# 07_eMMC.net
KiCad netlist of a schematic drawn in Altium Designer
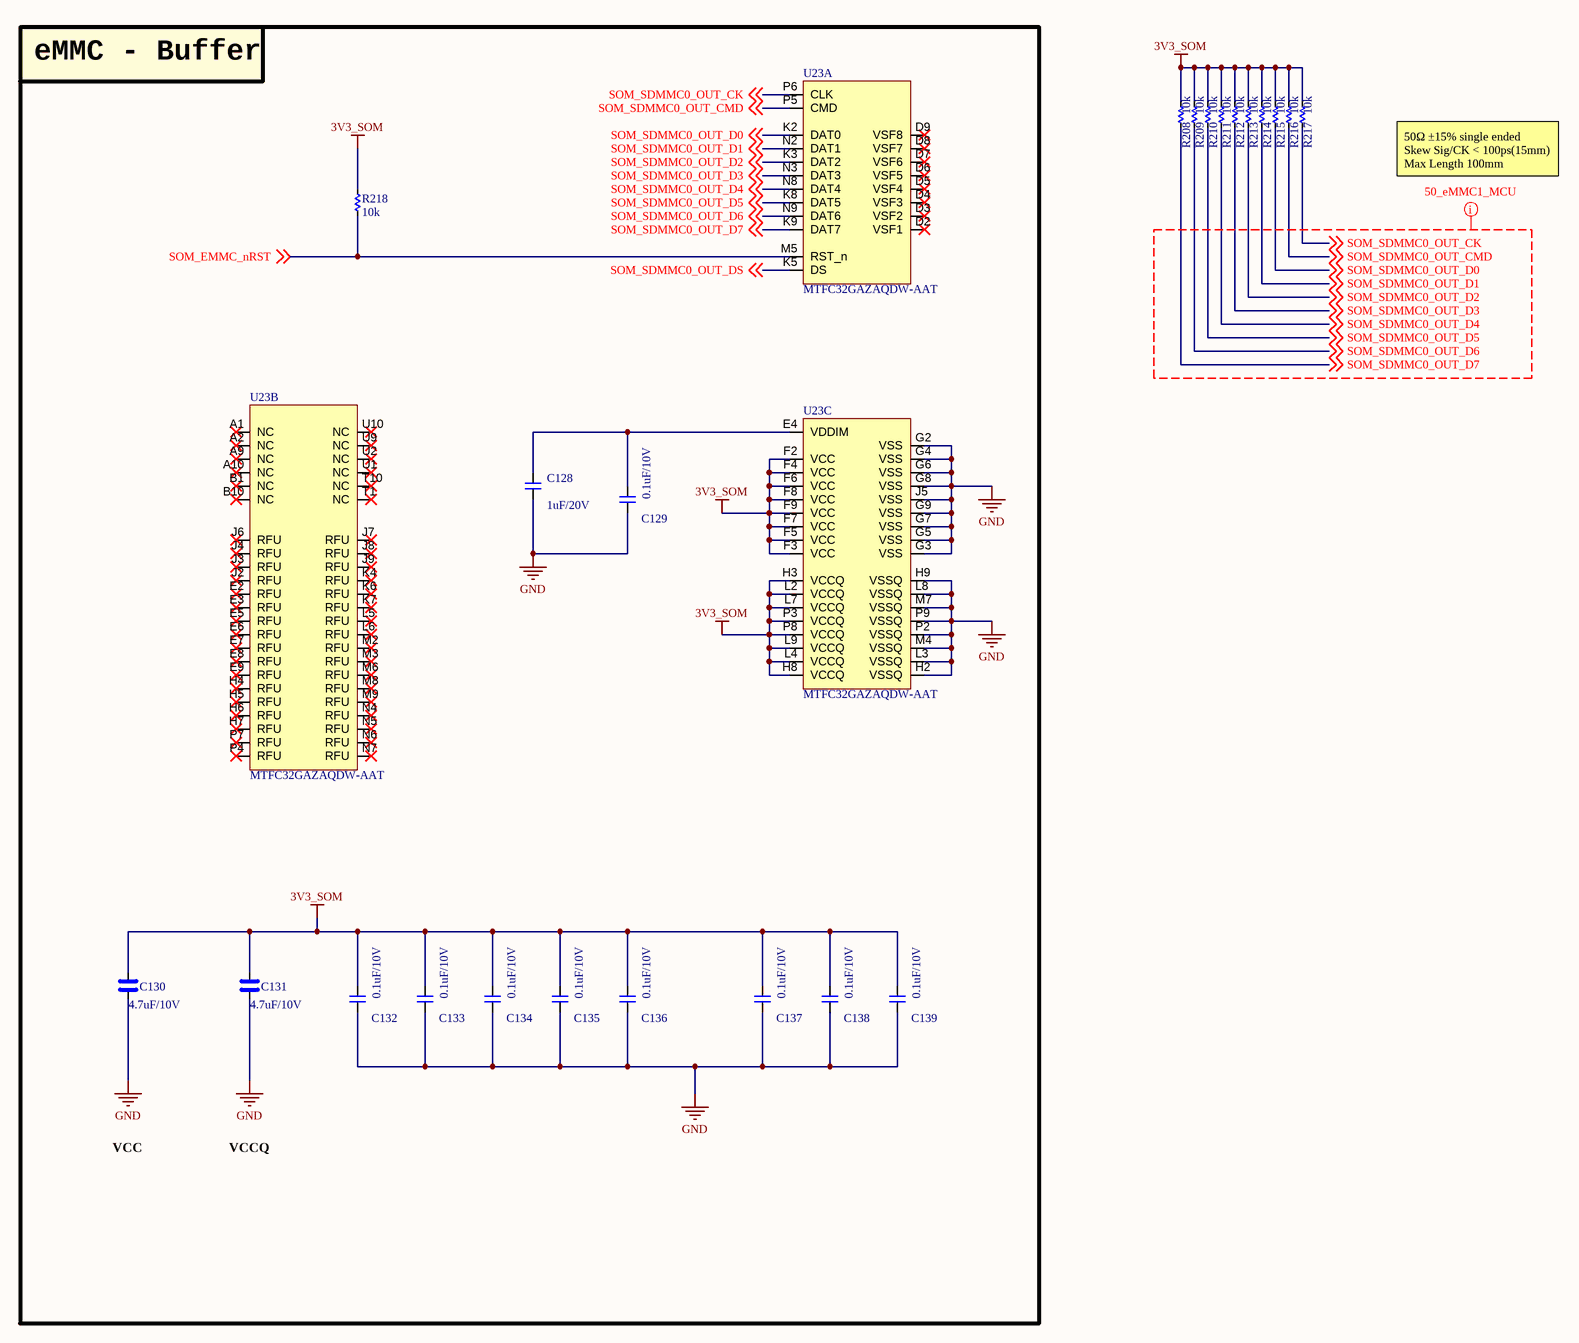
[diagram p0: 07_eMMC.SchDoc]

(export (version "E")
  (design (tool "Eeschema 10.0.6"))
  (components
    (comp (ref "C128")
      (value "1uF/20V")
      (footprint "CAP_C_1005X60")
      (description "CAP CHIP")
      (libsource (lib "LABLIB") (part "_CAP_C_2"))
    )
    (comp (ref "C129")
      (value "0.1uF/10V")
      (footprint "CAP_C_1005X60")
      (description "CAP CHIP")
      (libsource (lib "LABLIB") (part "_CAP_C_2"))
    )
    (comp (ref "C130")
      (value "4.7uF/10V")
      (footprint "CAP_C_1608X80")
      (description "CAP CHIP High Value")
      (libsource (lib "LABLIB") (part "_CAP_C_High_2"))
    )
    (comp (ref "C131")
      (value "4.7uF/10V")
      (footprint "CAP_C_1608X80")
      (description "CAP CHIP High Value")
      (libsource (lib "LABLIB") (part "_CAP_C_High_2"))
    )
    (comp (ref "C132")
      (value "0.1uF/10V")
      (footprint "CAP_C_1005X60")
      (description "CAP CHIP")
      (libsource (lib "LABLIB") (part "_CAP_C_2"))
    )
    (comp (ref "C133")
      (value "0.1uF/10V")
      (footprint "CAP_C_1005X60")
      (description "CAP CHIP")
      (libsource (lib "LABLIB") (part "_CAP_C_2"))
    )
    (comp (ref "C134")
      (value "0.1uF/10V")
      (footprint "CAP_C_1005X60")
      (description "CAP CHIP")
      (libsource (lib "LABLIB") (part "_CAP_C_2"))
    )
    (comp (ref "C135")
      (value "0.1uF/10V")
      (footprint "CAP_C_1005X60")
      (description "CAP CHIP")
      (libsource (lib "LABLIB") (part "_CAP_C_2"))
    )
    (comp (ref "C136")
      (value "0.1uF/10V")
      (footprint "CAP_C_1005X60")
      (description "CAP CHIP")
      (libsource (lib "LABLIB") (part "_CAP_C_2"))
    )
    (comp (ref "C137")
      (value "0.1uF/10V")
      (footprint "CAP_C_1005X60")
      (description "CAP CHIP")
      (libsource (lib "LABLIB") (part "_CAP_C_2"))
    )
    (comp (ref "C138")
      (value "0.1uF/10V")
      (footprint "CAP_C_1005X60")
      (description "CAP CHIP")
      (libsource (lib "LABLIB") (part "_CAP_C_2"))
    )
    (comp (ref "C139")
      (value "0.1uF/10V")
      (footprint "CAP_C_1005X60")
      (description "CAP CHIP")
      (libsource (lib "LABLIB") (part "_CAP_C_2"))
    )
    (comp (ref "R208")
      (value "10k")
      (footprint "RES_C_1005X40")
      (description "RES")
      (libsource (lib "LABLIB") (part "_RES_B_2"))
    )
    (comp (ref "R209")
      (value "10k")
      (footprint "RES_C_1005X40")
      (description "RES")
      (libsource (lib "LABLIB") (part "_RES_B_2"))
    )
    (comp (ref "R210")
      (value "10k")
      (footprint "RES_C_1005X40")
      (description "RES")
      (libsource (lib "LABLIB") (part "_RES_B_2"))
    )
    (comp (ref "R211")
      (value "10k")
      (footprint "RES_C_1005X40")
      (description "RES")
      (libsource (lib "LABLIB") (part "_RES_B_2"))
    )
    (comp (ref "R212")
      (value "10k")
      (footprint "RES_C_1005X40")
      (description "RES")
      (libsource (lib "LABLIB") (part "_RES_B_2"))
    )
    (comp (ref "R213")
      (value "10k")
      (footprint "RES_C_1005X40")
      (description "RES")
      (libsource (lib "LABLIB") (part "_RES_B_2"))
    )
    (comp (ref "R214")
      (value "10k")
      (footprint "RES_C_1005X40")
      (description "RES")
      (libsource (lib "LABLIB") (part "_RES_B_2"))
    )
    (comp (ref "R215")
      (value "10k")
      (footprint "RES_C_1005X40")
      (description "RES")
      (libsource (lib "LABLIB") (part "_RES_B_2"))
    )
    (comp (ref "R216")
      (value "10k")
      (footprint "RES_C_1005X40")
      (description "RES")
      (libsource (lib "LABLIB") (part "_RES_B_2"))
    )
    (comp (ref "R217")
      (value "10k")
      (footprint "RES_C_1005X40")
      (description "RES")
      (libsource (lib "LABLIB") (part "_RES_B_2"))
    )
    (comp (ref "R218")
      (value "10k")
      (footprint "RES_C_1005X40")
      (description "RES")
      (libsource (lib "LABLIB") (part "_RES_B_2"))
    )
    (comp (ref "U23")
      (value "MTFC32GAZAQDW-AAT")
      (footprint "BGA_100_C_100P_10X17_1400X1800X150")
      (libsource (lib "emmc_nofootprint") (part "MTFC32GAZAQDW-AAT"))
    )
  )
  (nets
    (net (code "1") (name "3V3_SOM") (class "Default")
      (node (ref "C130") (pin "2") (pinfunction "2_2") (pintype "passive"))
      (node (ref "C131") (pin "2") (pinfunction "2_2") (pintype "passive"))
      (node (ref "C132") (pin "2") (pinfunction "2_2") (pintype "passive"))
      (node (ref "C133") (pin "2") (pinfunction "2_2") (pintype "passive"))
      (node (ref "C134") (pin "2") (pinfunction "2_2") (pintype "passive"))
      (node (ref "C135") (pin "2") (pinfunction "2_2") (pintype "passive"))
      (node (ref "C136") (pin "2") (pinfunction "2_2") (pintype "passive"))
      (node (ref "C137") (pin "2") (pinfunction "2_2") (pintype "passive"))
      (node (ref "C138") (pin "2") (pinfunction "2_2") (pintype "passive"))
      (node (ref "C139") (pin "2") (pinfunction "2_2") (pintype "passive"))
      (node (ref "R208") (pin "2") (pinfunction "2_2") (pintype "passive"))
      (node (ref "R209") (pin "2") (pinfunction "2_2") (pintype "passive"))
      (node (ref "R210") (pin "2") (pinfunction "2_2") (pintype "passive"))
      (node (ref "R211") (pin "2") (pinfunction "2_2") (pintype "passive"))
      (node (ref "R212") (pin "2") (pinfunction "2_2") (pintype "passive"))
      (node (ref "R213") (pin "2") (pinfunction "2_2") (pintype "passive"))
      (node (ref "R214") (pin "2") (pinfunction "2_2") (pintype "passive"))
      (node (ref "R215") (pin "2") (pinfunction "2_2") (pintype "passive"))
      (node (ref "R216") (pin "2") (pinfunction "2_2") (pintype "passive"))
      (node (ref "R217") (pin "2") (pinfunction "2_2") (pintype "passive"))
      (node (ref "R218") (pin "2") (pinfunction "2_2") (pintype "passive"))
      (node (ref "U23") (pin "F2") (pinfunction "VCC_F2") (pintype "passive"))
      (node (ref "U23") (pin "F3") (pinfunction "VCC_F3") (pintype "passive"))
      (node (ref "U23") (pin "F4") (pinfunction "VCC_F4") (pintype "passive"))
      (node (ref "U23") (pin "F5") (pinfunction "VCC_F5") (pintype "passive"))
      (node (ref "U23") (pin "F6") (pinfunction "VCC_F6") (pintype "passive"))
      (node (ref "U23") (pin "F7") (pinfunction "VCC_F7") (pintype "passive"))
      (node (ref "U23") (pin "F8") (pinfunction "VCC_F8") (pintype "passive"))
      (node (ref "U23") (pin "F9") (pinfunction "VCC_F9") (pintype "passive"))
      (node (ref "U23") (pin "H3") (pinfunction "VCCQ_H3") (pintype "passive"))
      (node (ref "U23") (pin "H8") (pinfunction "VCCQ_H8") (pintype "passive"))
      (node (ref "U23") (pin "L2") (pinfunction "VCCQ_L2") (pintype "passive"))
      (node (ref "U23") (pin "L4") (pinfunction "VCCQ_L4") (pintype "passive"))
      (node (ref "U23") (pin "L7") (pinfunction "VCCQ_L7") (pintype "passive"))
      (node (ref "U23") (pin "L9") (pinfunction "VCCQ_L9") (pintype "passive"))
      (node (ref "U23") (pin "P3") (pinfunction "VCCQ_P3") (pintype "passive"))
      (node (ref "U23") (pin "P8") (pinfunction "VCCQ_P8") (pintype "passive"))
    )
    (net (code "2") (name "GND") (class "Default")
      (node (ref "C128") (pin "1") (pinfunction "1_1") (pintype "passive"))
      (node (ref "C129") (pin "1") (pinfunction "1_1") (pintype "passive"))
      (node (ref "C130") (pin "1") (pinfunction "1_1") (pintype "passive"))
      (node (ref "C131") (pin "1") (pinfunction "1_1") (pintype "passive"))
      (node (ref "C132") (pin "1") (pinfunction "1_1") (pintype "passive"))
      (node (ref "C133") (pin "1") (pinfunction "1_1") (pintype "passive"))
      (node (ref "C134") (pin "1") (pinfunction "1_1") (pintype "passive"))
      (node (ref "C135") (pin "1") (pinfunction "1_1") (pintype "passive"))
      (node (ref "C136") (pin "1") (pinfunction "1_1") (pintype "passive"))
      (node (ref "C137") (pin "1") (pinfunction "1_1") (pintype "passive"))
      (node (ref "C138") (pin "1") (pinfunction "1_1") (pintype "passive"))
      (node (ref "C139") (pin "1") (pinfunction "1_1") (pintype "passive"))
      (node (ref "U23") (pin "G2") (pinfunction "VSS_G2") (pintype "passive"))
      (node (ref "U23") (pin "G3") (pinfunction "VSS_G3") (pintype "passive"))
      (node (ref "U23") (pin "G4") (pinfunction "VSS_G4") (pintype "passive"))
      (node (ref "U23") (pin "G5") (pinfunction "VSS_G5") (pintype "passive"))
      (node (ref "U23") (pin "G6") (pinfunction "VSS_G6") (pintype "passive"))
      (node (ref "U23") (pin "G7") (pinfunction "VSS_G7") (pintype "passive"))
      (node (ref "U23") (pin "G8") (pinfunction "VSS_G8") (pintype "passive"))
      (node (ref "U23") (pin "G9") (pinfunction "VSS_G9") (pintype "passive"))
      (node (ref "U23") (pin "H2") (pinfunction "VSSQ_H2") (pintype "passive"))
      (node (ref "U23") (pin "H9") (pinfunction "VSSQ_H9") (pintype "passive"))
      (node (ref "U23") (pin "J5") (pinfunction "VSS_J5") (pintype "passive"))
      (node (ref "U23") (pin "L3") (pinfunction "VSSQ_L3") (pintype "passive"))
      (node (ref "U23") (pin "L8") (pinfunction "VSSQ_L8") (pintype "passive"))
      (node (ref "U23") (pin "M4") (pinfunction "VSSQ_M4") (pintype "passive"))
      (node (ref "U23") (pin "M7") (pinfunction "VSSQ_M7") (pintype "passive"))
      (node (ref "U23") (pin "P2") (pinfunction "VSSQ_P2") (pintype "passive"))
      (node (ref "U23") (pin "P9") (pinfunction "VSSQ_P9") (pintype "passive"))
    )
    (net (code "3") (name "Net-(U23C-VDDIM)") (class "Default")
      (node (ref "C128") (pin "2") (pinfunction "2_2") (pintype "passive"))
      (node (ref "C129") (pin "2") (pinfunction "2_2") (pintype "passive"))
      (node (ref "U23") (pin "E4") (pinfunction "VDDIM_E4") (pintype "passive"))
    )
    (net (code "4") (name "SOM_EMMC_nRST") (class "Default")
      (node (ref "R218") (pin "1") (pinfunction "1_1") (pintype "passive"))
      (node (ref "U23") (pin "M5") (pinfunction "RST_n_M5") (pintype "passive"))
    )
    (net (code "5") (name "SOM_SDMMC0_OUT_CK") (class "Default")
      (node (ref "R217") (pin "1") (pinfunction "1_1") (pintype "passive"))
      (node (ref "U23") (pin "P6") (pinfunction "CLK_P6") (pintype "passive"))
    )
    (net (code "6") (name "SOM_SDMMC0_OUT_CMD") (class "Default")
      (node (ref "R216") (pin "1") (pinfunction "1_1") (pintype "passive"))
      (node (ref "U23") (pin "P5") (pinfunction "CMD_P5") (pintype "passive"))
    )
    (net (code "7") (name "SOM_SDMMC0_OUT_D0") (class "Default")
      (node (ref "R215") (pin "1") (pinfunction "1_1") (pintype "passive"))
      (node (ref "U23") (pin "K2") (pinfunction "DAT0_K2") (pintype "passive"))
    )
    (net (code "8") (name "SOM_SDMMC0_OUT_D1") (class "Default")
      (node (ref "R214") (pin "1") (pinfunction "1_1") (pintype "passive"))
      (node (ref "U23") (pin "N2") (pinfunction "DAT1_N2") (pintype "passive"))
    )
    (net (code "9") (name "SOM_SDMMC0_OUT_D2") (class "Default")
      (node (ref "R213") (pin "1") (pinfunction "1_1") (pintype "passive"))
      (node (ref "U23") (pin "K3") (pinfunction "DAT2_K3") (pintype "passive"))
    )
    (net (code "10") (name "SOM_SDMMC0_OUT_D3") (class "Default")
      (node (ref "R212") (pin "1") (pinfunction "1_1") (pintype "passive"))
      (node (ref "U23") (pin "N3") (pinfunction "DAT3_N3") (pintype "passive"))
    )
    (net (code "11") (name "SOM_SDMMC0_OUT_D4") (class "Default")
      (node (ref "R211") (pin "1") (pinfunction "1_1") (pintype "passive"))
      (node (ref "U23") (pin "N8") (pinfunction "DAT4_N8") (pintype "passive"))
    )
    (net (code "12") (name "SOM_SDMMC0_OUT_D5") (class "Default")
      (node (ref "R210") (pin "1") (pinfunction "1_1") (pintype "passive"))
      (node (ref "U23") (pin "K8") (pinfunction "DAT5_K8") (pintype "passive"))
    )
    (net (code "13") (name "SOM_SDMMC0_OUT_D6") (class "Default")
      (node (ref "R209") (pin "1") (pinfunction "1_1") (pintype "passive"))
      (node (ref "U23") (pin "N9") (pinfunction "DAT6_N9") (pintype "passive"))
    )
    (net (code "14") (name "SOM_SDMMC0_OUT_D7") (class "Default")
      (node (ref "R208") (pin "1") (pinfunction "1_1") (pintype "passive"))
      (node (ref "U23") (pin "K9") (pinfunction "DAT7_K9") (pintype "passive"))
    )
    (net (code "15") (name "SOM_SDMMC0_OUT_DS") (class "Default")
      (node (ref "U23") (pin "K5") (pinfunction "DS_K5") (pintype "passive"))
    )
    (net (code "16") (name "unconnected-(U23A-VSF1-PadD2)") (class "Default")
      (node (ref "U23") (pin "D2") (pinfunction "VSF1_D2") (pintype "passive+no_connect"))
    )
    (net (code "17") (name "unconnected-(U23A-VSF2-PadD3)") (class "Default")
      (node (ref "U23") (pin "D3") (pinfunction "VSF2_D3") (pintype "passive+no_connect"))
    )
    (net (code "18") (name "unconnected-(U23A-VSF3-PadD4)") (class "Default")
      (node (ref "U23") (pin "D4") (pinfunction "VSF3_D4") (pintype "passive+no_connect"))
    )
    (net (code "19") (name "unconnected-(U23A-VSF4-PadD5)") (class "Default")
      (node (ref "U23") (pin "D5") (pinfunction "VSF4_D5") (pintype "passive+no_connect"))
    )
    (net (code "20") (name "unconnected-(U23A-VSF5-PadD6)") (class "Default")
      (node (ref "U23") (pin "D6") (pinfunction "VSF5_D6") (pintype "passive+no_connect"))
    )
    (net (code "21") (name "unconnected-(U23A-VSF6-PadD7)") (class "Default")
      (node (ref "U23") (pin "D7") (pinfunction "VSF6_D7") (pintype "passive+no_connect"))
    )
    (net (code "22") (name "unconnected-(U23A-VSF7-PadD8)") (class "Default")
      (node (ref "U23") (pin "D8") (pinfunction "VSF7_D8") (pintype "passive+no_connect"))
    )
    (net (code "23") (name "unconnected-(U23A-VSF8-PadD9)") (class "Default")
      (node (ref "U23") (pin "D9") (pinfunction "VSF8_D9") (pintype "passive+no_connect"))
    )
    (net (code "24") (name "unconnected-(U23B-NC-PadA1)") (class "Default")
      (node (ref "U23") (pin "A1") (pinfunction "NC_A1") (pintype "passive+no_connect"))
    )
    (net (code "25") (name "unconnected-(U23B-NC-PadA2)") (class "Default")
      (node (ref "U23") (pin "A2") (pinfunction "NC_A2") (pintype "passive+no_connect"))
    )
    (net (code "26") (name "unconnected-(U23B-NC-PadA9)") (class "Default")
      (node (ref "U23") (pin "A9") (pinfunction "NC_A9") (pintype "passive+no_connect"))
    )
    (net (code "27") (name "unconnected-(U23B-NC-PadA10)") (class "Default")
      (node (ref "U23") (pin "A10") (pinfunction "NC_A10") (pintype "passive+no_connect"))
    )
    (net (code "28") (name "unconnected-(U23B-NC-PadB1)") (class "Default")
      (node (ref "U23") (pin "B1") (pinfunction "NC_B1") (pintype "passive+no_connect"))
    )
    (net (code "29") (name "unconnected-(U23B-NC-PadB10)") (class "Default")
      (node (ref "U23") (pin "B10") (pinfunction "NC_B10") (pintype "passive+no_connect"))
    )
    (net (code "30") (name "unconnected-(U23B-NC-PadT1)") (class "Default")
      (node (ref "U23") (pin "T1") (pinfunction "NC_T1") (pintype "passive+no_connect"))
    )
    (net (code "31") (name "unconnected-(U23B-NC-PadT10)") (class "Default")
      (node (ref "U23") (pin "T10") (pinfunction "NC_T10") (pintype "passive+no_connect"))
    )
    (net (code "32") (name "unconnected-(U23B-NC-PadU1)") (class "Default")
      (node (ref "U23") (pin "U1") (pinfunction "NC_U1") (pintype "passive+no_connect"))
    )
    (net (code "33") (name "unconnected-(U23B-NC-PadU2)") (class "Default")
      (node (ref "U23") (pin "U2") (pinfunction "NC_U2") (pintype "passive+no_connect"))
    )
    (net (code "34") (name "unconnected-(U23B-NC-PadU9)") (class "Default")
      (node (ref "U23") (pin "U9") (pinfunction "NC_U9") (pintype "passive+no_connect"))
    )
    (net (code "35") (name "unconnected-(U23B-NC-PadU10)") (class "Default")
      (node (ref "U23") (pin "U10") (pinfunction "NC_U10") (pintype "passive+no_connect"))
    )
    (net (code "36") (name "unconnected-(U23B-RFU-PadE2)") (class "Default")
      (node (ref "U23") (pin "E2") (pinfunction "RFU_E2") (pintype "passive+no_connect"))
    )
    (net (code "37") (name "unconnected-(U23B-RFU-PadE3)") (class "Default")
      (node (ref "U23") (pin "E3") (pinfunction "RFU_E3") (pintype "passive+no_connect"))
    )
    (net (code "38") (name "unconnected-(U23B-RFU-PadE5)") (class "Default")
      (node (ref "U23") (pin "E5") (pinfunction "RFU_E5") (pintype "passive+no_connect"))
    )
    (net (code "39") (name "unconnected-(U23B-RFU-PadE6)") (class "Default")
      (node (ref "U23") (pin "E6") (pinfunction "RFU_E6") (pintype "passive+no_connect"))
    )
    (net (code "40") (name "unconnected-(U23B-RFU-PadE7)") (class "Default")
      (node (ref "U23") (pin "E7") (pinfunction "RFU_E7") (pintype "passive+no_connect"))
    )
    (net (code "41") (name "unconnected-(U23B-RFU-PadE8)") (class "Default")
      (node (ref "U23") (pin "E8") (pinfunction "RFU_E8") (pintype "passive+no_connect"))
    )
    (net (code "42") (name "unconnected-(U23B-RFU-PadE9)") (class "Default")
      (node (ref "U23") (pin "E9") (pinfunction "RFU_E9") (pintype "passive+no_connect"))
    )
    (net (code "43") (name "unconnected-(U23B-RFU-PadH4)") (class "Default")
      (node (ref "U23") (pin "H4") (pinfunction "RFU_H4") (pintype "passive+no_connect"))
    )
    (net (code "44") (name "unconnected-(U23B-RFU-PadH5)") (class "Default")
      (node (ref "U23") (pin "H5") (pinfunction "RFU_H5") (pintype "passive+no_connect"))
    )
    (net (code "45") (name "unconnected-(U23B-RFU-PadH6)") (class "Default")
      (node (ref "U23") (pin "H6") (pinfunction "RFU_H6") (pintype "passive+no_connect"))
    )
    (net (code "46") (name "unconnected-(U23B-RFU-PadH7)") (class "Default")
      (node (ref "U23") (pin "H7") (pinfunction "RFU_H7") (pintype "passive+no_connect"))
    )
    (net (code "47") (name "unconnected-(U23B-RFU-PadJ2)") (class "Default")
      (node (ref "U23") (pin "J2") (pinfunction "RFU_J2") (pintype "passive+no_connect"))
    )
    (net (code "48") (name "unconnected-(U23B-RFU-PadJ3)") (class "Default")
      (node (ref "U23") (pin "J3") (pinfunction "RFU_J3") (pintype "passive+no_connect"))
    )
    (net (code "49") (name "unconnected-(U23B-RFU-PadJ4)") (class "Default")
      (node (ref "U23") (pin "J4") (pinfunction "RFU_J4") (pintype "passive+no_connect"))
    )
    (net (code "50") (name "unconnected-(U23B-RFU-PadJ6)") (class "Default")
      (node (ref "U23") (pin "J6") (pinfunction "RFU_J6") (pintype "passive+no_connect"))
    )
    (net (code "51") (name "unconnected-(U23B-RFU-PadJ7)") (class "Default")
      (node (ref "U23") (pin "J7") (pinfunction "RFU_J7") (pintype "passive+no_connect"))
    )
    (net (code "52") (name "unconnected-(U23B-RFU-PadJ8)") (class "Default")
      (node (ref "U23") (pin "J8") (pinfunction "RFU_J8") (pintype "passive+no_connect"))
    )
    (net (code "53") (name "unconnected-(U23B-RFU-PadJ9)") (class "Default")
      (node (ref "U23") (pin "J9") (pinfunction "RFU_J9") (pintype "passive+no_connect"))
    )
    (net (code "54") (name "unconnected-(U23B-RFU-PadK4)") (class "Default")
      (node (ref "U23") (pin "K4") (pinfunction "RFU_K4") (pintype "passive+no_connect"))
    )
    (net (code "55") (name "unconnected-(U23B-RFU-PadK6)") (class "Default")
      (node (ref "U23") (pin "K6") (pinfunction "RFU_K6") (pintype "passive+no_connect"))
    )
    (net (code "56") (name "unconnected-(U23B-RFU-PadK7)") (class "Default")
      (node (ref "U23") (pin "K7") (pinfunction "RFU_K7") (pintype "passive+no_connect"))
    )
    (net (code "57") (name "unconnected-(U23B-RFU-PadL5)") (class "Default")
      (node (ref "U23") (pin "L5") (pinfunction "RFU_L5") (pintype "passive+no_connect"))
    )
    (net (code "58") (name "unconnected-(U23B-RFU-PadL6)") (class "Default")
      (node (ref "U23") (pin "L6") (pinfunction "RFU_L6") (pintype "passive+no_connect"))
    )
    (net (code "59") (name "unconnected-(U23B-RFU-PadM2)") (class "Default")
      (node (ref "U23") (pin "M2") (pinfunction "RFU_M2") (pintype "passive+no_connect"))
    )
    (net (code "60") (name "unconnected-(U23B-RFU-PadM3)") (class "Default")
      (node (ref "U23") (pin "M3") (pinfunction "RFU_M3") (pintype "passive+no_connect"))
    )
    (net (code "61") (name "unconnected-(U23B-RFU-PadM6)") (class "Default")
      (node (ref "U23") (pin "M6") (pinfunction "RFU_M6") (pintype "passive+no_connect"))
    )
    (net (code "62") (name "unconnected-(U23B-RFU-PadM8)") (class "Default")
      (node (ref "U23") (pin "M8") (pinfunction "RFU_M8") (pintype "passive+no_connect"))
    )
    (net (code "63") (name "unconnected-(U23B-RFU-PadM9)") (class "Default")
      (node (ref "U23") (pin "M9") (pinfunction "RFU_M9") (pintype "passive+no_connect"))
    )
    (net (code "64") (name "unconnected-(U23B-RFU-PadN4)") (class "Default")
      (node (ref "U23") (pin "N4") (pinfunction "RFU_N4") (pintype "passive+no_connect"))
    )
    (net (code "65") (name "unconnected-(U23B-RFU-PadN5)") (class "Default")
      (node (ref "U23") (pin "N5") (pinfunction "RFU_N5") (pintype "passive+no_connect"))
    )
    (net (code "66") (name "unconnected-(U23B-RFU-PadN6)") (class "Default")
      (node (ref "U23") (pin "N6") (pinfunction "RFU_N6") (pintype "passive+no_connect"))
    )
    (net (code "67") (name "unconnected-(U23B-RFU-PadN7)") (class "Default")
      (node (ref "U23") (pin "N7") (pinfunction "RFU_N7") (pintype "passive+no_connect"))
    )
    (net (code "68") (name "unconnected-(U23B-RFU-PadP4)") (class "Default")
      (node (ref "U23") (pin "P4") (pinfunction "RFU_P4") (pintype "passive+no_connect"))
    )
    (net (code "69") (name "unconnected-(U23B-RFU-PadP7)") (class "Default")
      (node (ref "U23") (pin "P7") (pinfunction "RFU_P7") (pintype "passive+no_connect"))
    )
  )
)
